# TTR1_Gr4_-_SIMON_Timoth_e_Testeur.net
KiCad netlist of a schematic drawn in EAGLE
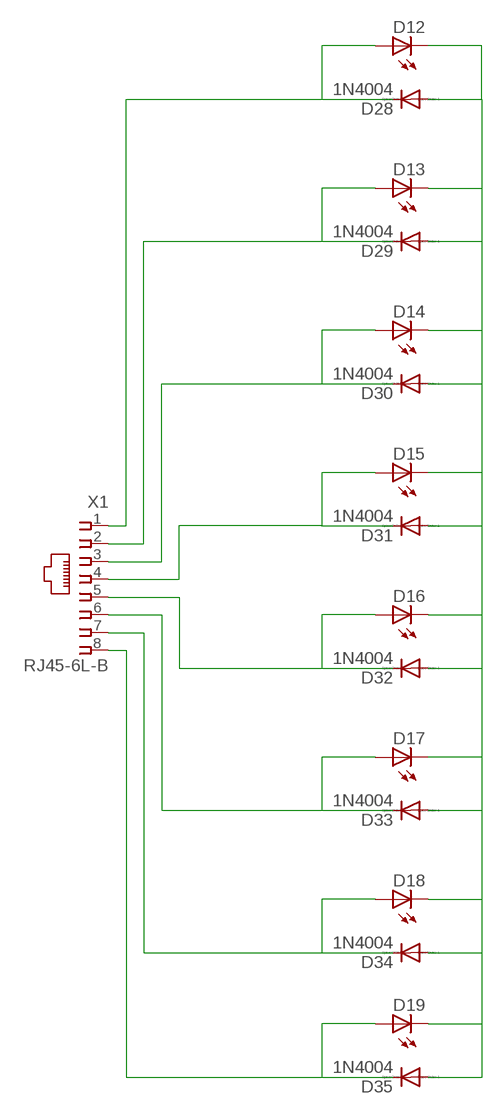
[diagram p0: schematic, sheet 1]

(export (version "E")
  (design (tool "Eeschema 10.0.6"))
  (components
    (comp (ref "D12")
      (value "LED5MM")
      (footprint "eagle-import:LED5MM")
      (libsource (lib "eagle-import") (part "LED5MM"))
    )
    (comp (ref "D13")
      (value "LED5MM")
      (footprint "eagle-import:LED5MM")
      (libsource (lib "eagle-import") (part "LED5MM"))
    )
    (comp (ref "D14")
      (value "LED5MM")
      (footprint "eagle-import:LED5MM")
      (libsource (lib "eagle-import") (part "LED5MM"))
    )
    (comp (ref "D15")
      (value "LED5MM")
      (footprint "eagle-import:LED5MM")
      (libsource (lib "eagle-import") (part "LED5MM"))
    )
    (comp (ref "D16")
      (value "LED5MM")
      (footprint "eagle-import:LED5MM")
      (libsource (lib "eagle-import") (part "LED5MM"))
    )
    (comp (ref "D17")
      (value "LED5MM")
      (footprint "eagle-import:LED5MM")
      (libsource (lib "eagle-import") (part "LED5MM"))
    )
    (comp (ref "D18")
      (value "LED5MM")
      (footprint "eagle-import:LED5MM")
      (libsource (lib "eagle-import") (part "LED5MM"))
    )
    (comp (ref "D19")
      (value "LED5MM")
      (footprint "eagle-import:LED5MM")
      (libsource (lib "eagle-import") (part "LED5MM"))
    )
    (comp (ref "D28")
      (value "1N4004")
      (footprint "eagle-import:DO41-10")
      (libsource (lib "eagle-import") (part "1N4004"))
    )
    (comp (ref "D29")
      (value "1N4004")
      (footprint "eagle-import:DO41-10")
      (libsource (lib "eagle-import") (part "1N4004"))
    )
    (comp (ref "D30")
      (value "1N4004")
      (footprint "eagle-import:DO41-10")
      (libsource (lib "eagle-import") (part "1N4004"))
    )
    (comp (ref "D31")
      (value "1N4004")
      (footprint "eagle-import:DO41-10")
      (libsource (lib "eagle-import") (part "1N4004"))
    )
    (comp (ref "D32")
      (value "1N4004")
      (footprint "eagle-import:DO41-10")
      (libsource (lib "eagle-import") (part "1N4004"))
    )
    (comp (ref "D33")
      (value "1N4004")
      (footprint "eagle-import:DO41-10")
      (libsource (lib "eagle-import") (part "1N4004"))
    )
    (comp (ref "D34")
      (value "1N4004")
      (footprint "eagle-import:DO41-10")
      (libsource (lib "eagle-import") (part "1N4004"))
    )
    (comp (ref "D35")
      (value "1N4004")
      (footprint "eagle-import:DO41-10")
      (libsource (lib "eagle-import") (part "1N4004"))
    )
    (comp (ref "X1")
      (value "RJ45-6L-B")
      (footprint "eagle-import:RJ45-NO-SHIELD")
      (libsource (lib "eagle-import") (part "RJ45-6L-B"))
    )
  )
  (nets
    (net (code "1") (name "Net-(D12-C)") (class "Default")
      (node (ref "D12") (pin "K") (pinfunction "C_K") (pintype "passive"))
      (node (ref "D13") (pin "K") (pinfunction "C_K") (pintype "passive"))
      (node (ref "D14") (pin "K") (pinfunction "C_K") (pintype "passive"))
      (node (ref "D15") (pin "K") (pinfunction "C_K") (pintype "passive"))
      (node (ref "D16") (pin "K") (pinfunction "C_K") (pintype "passive"))
      (node (ref "D17") (pin "K") (pinfunction "C_K") (pintype "passive"))
      (node (ref "D18") (pin "K") (pinfunction "C_K") (pintype "passive"))
      (node (ref "D19") (pin "K") (pinfunction "C_K") (pintype "passive"))
      (node (ref "D28") (pin "A") (pinfunction "A_A") (pintype "passive"))
      (node (ref "D29") (pin "A") (pinfunction "A_A") (pintype "passive"))
      (node (ref "D30") (pin "A") (pinfunction "A_A") (pintype "passive"))
      (node (ref "D31") (pin "A") (pinfunction "A_A") (pintype "passive"))
      (node (ref "D32") (pin "A") (pinfunction "A_A") (pintype "passive"))
      (node (ref "D33") (pin "A") (pinfunction "A_A") (pintype "passive"))
      (node (ref "D34") (pin "A") (pinfunction "A_A") (pintype "passive"))
      (node (ref "D35") (pin "A") (pinfunction "A_A") (pintype "passive"))
    )
    (net (code "2") (name "Net-(D12-PadA)") (class "Default")
      (node (ref "D12") (pin "A") (pinfunction "A_A") (pintype "passive"))
      (node (ref "D28") (pin "C") (pinfunction "C_C") (pintype "passive"))
      (node (ref "X1") (pin "1") (pinfunction "1_1") (pintype "passive"))
    )
    (net (code "3") (name "Net-(D13-PadA)") (class "Default")
      (node (ref "D13") (pin "A") (pinfunction "A_A") (pintype "passive"))
      (node (ref "D29") (pin "C") (pinfunction "C_C") (pintype "passive"))
      (node (ref "X1") (pin "2") (pinfunction "2_2") (pintype "passive"))
    )
    (net (code "4") (name "Net-(D14-PadA)") (class "Default")
      (node (ref "D14") (pin "A") (pinfunction "A_A") (pintype "passive"))
      (node (ref "D30") (pin "C") (pinfunction "C_C") (pintype "passive"))
      (node (ref "X1") (pin "3") (pinfunction "3_3") (pintype "passive"))
    )
    (net (code "5") (name "Net-(D15-PadA)") (class "Default")
      (node (ref "D15") (pin "A") (pinfunction "A_A") (pintype "passive"))
      (node (ref "D31") (pin "C") (pinfunction "C_C") (pintype "passive"))
      (node (ref "X1") (pin "4") (pinfunction "4_4") (pintype "passive"))
    )
    (net (code "6") (name "Net-(D16-PadA)") (class "Default")
      (node (ref "D16") (pin "A") (pinfunction "A_A") (pintype "passive"))
      (node (ref "D32") (pin "C") (pinfunction "C_C") (pintype "passive"))
      (node (ref "X1") (pin "5") (pinfunction "5_5") (pintype "passive"))
    )
    (net (code "7") (name "Net-(D17-PadA)") (class "Default")
      (node (ref "D17") (pin "A") (pinfunction "A_A") (pintype "passive"))
      (node (ref "D33") (pin "C") (pinfunction "C_C") (pintype "passive"))
      (node (ref "X1") (pin "6") (pinfunction "6_6") (pintype "passive"))
    )
    (net (code "8") (name "Net-(D18-PadA)") (class "Default")
      (node (ref "D18") (pin "A") (pinfunction "A_A") (pintype "passive"))
      (node (ref "D34") (pin "C") (pinfunction "C_C") (pintype "passive"))
      (node (ref "X1") (pin "7") (pinfunction "7_7") (pintype "passive"))
    )
    (net (code "9") (name "Net-(D19-PadA)") (class "Default")
      (node (ref "D19") (pin "A") (pinfunction "A_A") (pintype "passive"))
      (node (ref "D35") (pin "C") (pinfunction "C_C") (pintype "passive"))
      (node (ref "X1") (pin "8") (pinfunction "8_8") (pintype "passive"))
    )
  )
)
